# TOP.net
KiCad netlist of a schematic drawn in Altium Designer
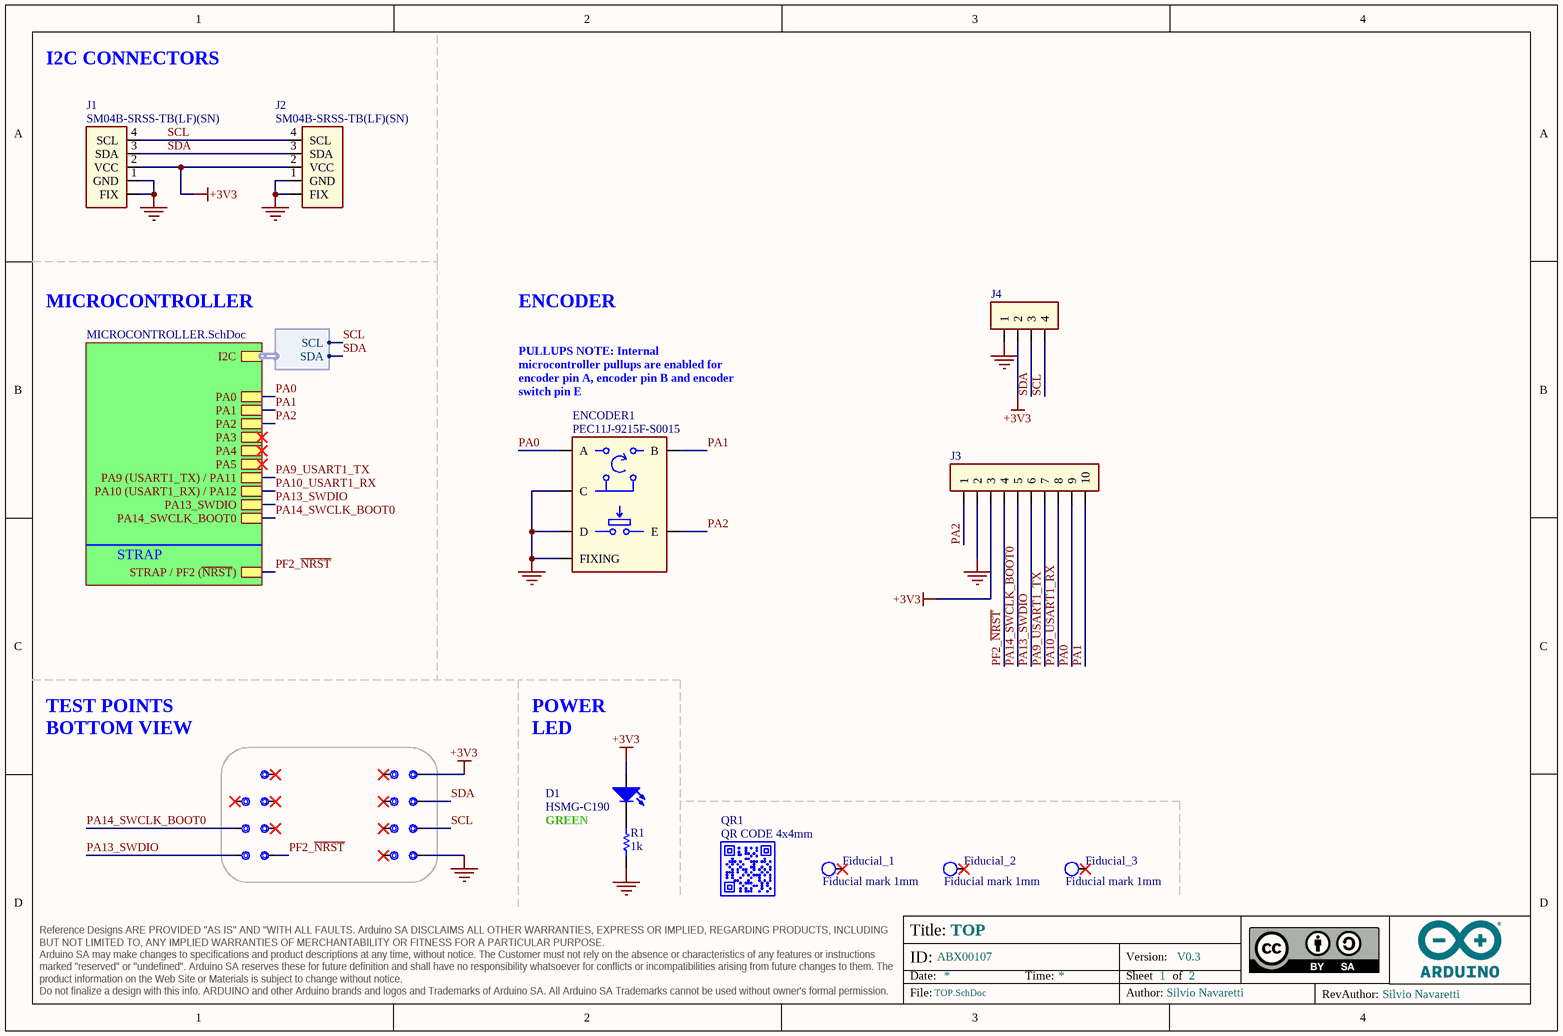
[diagram p0: TOP.SchDoc]

(export (version "E")
  (design (tool "Eeschema 10.0.6"))
  (components
    (comp (ref "3V3")
      (value "Test point 1.00mm")
      (footprint "TP-1.00MM")
      (fields (field (name "MANUFACTURER") "This is not a component"))
      (libsource (lib "Clean") (part "TESTPOINT"))
    )
    (comp (ref "D1")
      (value "HSMG-C190")
      (footprint "LEDC1608X80N-AK")
      (description "LED SMD 0603 GREEN/568 15mcd 120^")
      (fields (field (name "MANUFACTURER") "Broadcom"))
      (libsource (lib "Clean") (part "LED"))
    )
    (comp (ref "ENCODER1")
      (value "PEC11J-9215F-S0015")
      (footprint "PEC11J-9215F-S0015")
      (description "ENCODER 2b quadrature, 15PPR, 30 detents, shaft 15mm D-Cut, switch 350+-100gf, SMD 15x18x20mm")
      (fields (field (name "MANUFACTURER") "Bourns"))
      (libsource (lib "Clean") (part "PEC11J-9215F-S0015"))
    )
    (comp (ref "Fiducial_1")
      (value "Fiducial mark 1mm")
      (footprint "Fiducial mark 1mm-Footprint-1")
      (description "Fiducial mark 1mm clearance 2mm")
      (libsource (lib "Clean") (part "Fiducial mark 1mm"))
    )
    (comp (ref "Fiducial_2")
      (value "Fiducial mark 1mm")
      (footprint "Fiducial mark 1mm-Footprint-1")
      (description "Fiducial mark 1mm clearance 2mm")
      (libsource (lib "Clean") (part "Fiducial mark 1mm"))
    )
    (comp (ref "Fiducial_3")
      (value "Fiducial mark 1mm")
      (footprint "Fiducial mark 1mm-Footprint-1")
      (description "Fiducial mark 1mm clearance 2mm")
      (libsource (lib "Clean") (part "Fiducial mark 1mm"))
    )
    (comp (ref "GND")
      (value "Test point 1.00mm")
      (footprint "TP-1.00MM")
      (fields (field (name "MANUFACTURER") "This is not a component"))
      (libsource (lib "Clean") (part "TESTPOINT"))
    )
    (comp (ref "J1")
      (value "SM04B-SRSS-TB(LF)(SN)")
      (footprint "SM04B-SRSS-TB(LF)(SN)-Footprint-1")
      (description "CONN JST 4POS SIDE 1MM TIN QWIIC")
      (fields (field (name "MANUFACTURER") "JST"))
      (libsource (lib "") (part "SM04B-SRSS-TB(LF)(SN)_1"))
    )
    (comp (ref "J2")
      (value "SM04B-SRSS-TB(LF)(SN)")
      (footprint "SM04B-SRSS-TB(LF)(SN)-Footprint-1")
      (description "CONN JST 4POS SIDE 1MM TIN QWIIC")
      (fields (field (name "MANUFACTURER") "JST"))
      (libsource (lib "Clean") (part "SM04B-SRSS-TB(LF)(SN)"))
    )
    (comp (ref "J3")
      (value "HEADER TH 2.54mm VERT. 1x010POS")
      (footprint "PIN HEADER 2.54mm VERT. 1x10POS")
      (libsource (lib "Clean") (part "PIN HEADER 2.54mm VERT. 1x10POS"))
    )
    (comp (ref "J4")
      (value "HEADER TH 2.54mm VERT. 1x004POS")
      (footprint "PIN HEADER 2.54mm VERT. 1x4POS-Footprint-1")
      (libsource (lib "Clean") (part "PIN HEADER 2.54mm VERT. 1x4POS"))
    )
    (comp (ref "NRST")
      (value "Test point 1.00mm")
      (footprint "TP-1.00MM")
      (fields (field (name "MANUFACTURER") "This is not a component"))
      (libsource (lib "Clean") (part "TESTPOINT"))
    )
    (comp (ref "PA6")
      (value "Test point 1.00mm")
      (footprint "TP-1.00MM")
      (fields (field (name "MANUFACTURER") "This is not a component"))
      (libsource (lib "Clean") (part "TESTPOINT"))
    )
    (comp (ref "PA7")
      (value "Test point 1.00mm")
      (footprint "TP-1.00MM")
      (fields (field (name "MANUFACTURER") "This is not a component"))
      (libsource (lib "Clean") (part "TESTPOINT"))
    )
    (comp (ref "PC14")
      (value "Test point 1.00mm")
      (footprint "TP-1.00MM")
      (fields (field (name "MANUFACTURER") "This is not a component"))
      (libsource (lib "Clean") (part "TESTPOINT"))
    )
    (comp (ref "PC15")
      (value "Test point 1.00mm")
      (footprint "TP-1.00MM")
      (fields (field (name "MANUFACTURER") "This is not a component"))
      (libsource (lib "Clean") (part "TESTPOINT"))
    )
    (comp (ref "QR1")
      (value "QR CODE 4x4mm")
      (footprint "QR CODE 4x4mm")
      (description "QR CODE 4x4mm on layer 34 (This is not a component)")
      (fields (field (name "PART NUMBER") "This is not a component"))
      (libsource (lib "Clean") (part "QR CODE 4x4mm"))
    )
    (comp (ref "R1")
      (value "1k")
      (footprint "RES-0402")
      (description "RES CHIP 0402 1k 1% 1/16W")
      (fields (field (name "PART NUMBER") "CRCW04021K00FKEDC") (field (name "TOLERANCE") "1%"))
      (libsource (lib "Clean") (part "RES"))
    )
    (comp (ref "SCL")
      (value "Test point 1.00mm")
      (footprint "TP-1.00MM")
      (fields (field (name "MANUFACTURER") "This is not a component"))
      (libsource (lib "Clean") (part "TESTPOINT"))
    )
    (comp (ref "SDA")
      (value "Test point 1.00mm")
      (footprint "TP-1.00MM")
      (fields (field (name "MANUFACTURER") "This is not a component"))
      (libsource (lib "Clean") (part "TESTPOINT"))
    )
    (comp (ref "SWCLK")
      (value "Test point 1.00mm")
      (footprint "TP-1.00MM")
      (fields (field (name "MANUFACTURER") "This is not a component"))
      (libsource (lib "Clean") (part "TESTPOINT"))
    )
    (comp (ref "SWDIO")
      (value "Test point 1.00mm")
      (footprint "TP-1.00MM")
      (fields (field (name "MANUFACTURER") "This is not a component"))
      (libsource (lib "Clean") (part "TESTPOINT"))
    )
    (comp (ref "TP9")
      (value "Test point 1.00mm")
      (footprint "TP-1.00MM")
      (fields (field (name "MANUFACTURER") "This is not a component"))
      (libsource (lib "Clean") (part "TESTPOINT"))
    )
    (comp (ref "TP10")
      (value "Test point 1.00mm")
      (footprint "TP-1.00MM")
      (fields (field (name "MANUFACTURER") "This is not a component"))
      (libsource (lib "Clean") (part "TESTPOINT"))
    )
    (comp (ref "TP11")
      (value "Test point 1.00mm")
      (footprint "TP-1.00MM")
      (fields (field (name "MANUFACTURER") "This is not a component"))
      (libsource (lib "Clean") (part "TESTPOINT"))
    )
    (comp (ref "TP12")
      (value "Test point 1.00mm")
      (footprint "TP-1.00MM")
      (fields (field (name "MANUFACTURER") "This is not a component"))
      (libsource (lib "Clean") (part "TESTPOINT"))
    )
  )
  (nets
    (net (code "2") (name "+3V3") (class "Default")
      (node (ref "3V3") (pin "X") (pinfunction "X_X") (pintype "passive"))
      (node (ref "D1") (pin "A") (pinfunction "A_A") (pintype "passive"))
      (node (ref "J1") (pin "2") (pinfunction "VCC_2") (pintype "passive"))
      (node (ref "J2") (pin "2") (pinfunction "VCC_2") (pintype "passive"))
      (node (ref "J3") (pin "3") (pinfunction "3_3") (pintype "passive"))
      (node (ref "J4") (pin "2") (pinfunction "2_2") (pintype "passive"))
    )
    (net (code "3") (name "/PA0") (class "Default")
      (node (ref "ENCODER1") (pin "A") (pinfunction "A_A") (pintype "passive"))
      (node (ref "J3") (pin "9") (pinfunction "9_9") (pintype "passive"))
    )
    (net (code "4") (name "/PA1") (class "Default")
      (node (ref "ENCODER1") (pin "B") (pinfunction "B_B") (pintype "passive"))
      (node (ref "J3") (pin "10") (pinfunction "10_10") (pintype "passive"))
    )
    (net (code "5") (name "/PA2") (class "Default")
      (node (ref "ENCODER1") (pin "E") (pinfunction "E_E") (pintype "passive"))
      (node (ref "J3") (pin "1") (pinfunction "1_1") (pintype "passive"))
    )
    (net (code "9") (name "/PA9_USART1_TX") (class "Default")
      (node (ref "J3") (pin "7") (pinfunction "7_7") (pintype "passive"))
    )
    (net (code "10") (name "/PA10_USART1_RX") (class "Default")
      (node (ref "J3") (pin "8") (pinfunction "8_8") (pintype "passive"))
    )
    (net (code "11") (name "/PA13_SWDIO") (class "Default")
      (node (ref "J3") (pin "6") (pinfunction "6_6") (pintype "passive"))
      (node (ref "SWCLK") (pin "X") (pinfunction "X_X") (pintype "passive"))
    )
    (net (code "12") (name "/PA14_SWCLK_BOOT0") (class "Default")
      (node (ref "J3") (pin "5") (pinfunction "5_5") (pintype "passive"))
      (node (ref "SWDIO") (pin "X") (pinfunction "X_X") (pintype "passive"))
    )
    (net (code "13") (name "/PF2_~{NRST}") (class "Default")
      (node (ref "J3") (pin "4") (pinfunction "4_4") (pintype "passive"))
      (node (ref "NRST") (pin "X") (pinfunction "X_X") (pintype "passive"))
    )
    (net (code "14") (name "/SCL") (class "Default")
      (node (ref "J1") (pin "4") (pinfunction "SCL_4") (pintype "passive"))
      (node (ref "J2") (pin "4") (pinfunction "SCL_4") (pintype "passive"))
      (node (ref "J4") (pin "4") (pinfunction "4_4") (pintype "passive"))
      (node (ref "SCL") (pin "X") (pinfunction "X_X") (pintype "passive"))
    )
    (net (code "15") (name "/SDA") (class "Default")
      (node (ref "J1") (pin "3") (pinfunction "SDA_3") (pintype "passive"))
      (node (ref "J2") (pin "3") (pinfunction "SDA_3") (pintype "passive"))
      (node (ref "J4") (pin "3") (pinfunction "3_3") (pintype "passive"))
      (node (ref "SDA") (pin "X") (pinfunction "X_X") (pintype "passive"))
    )
    (net (code "17") (name "GND") (class "Default")
      (node (ref "ENCODER1") (pin "C") (pinfunction "C_C") (pintype "passive"))
      (node (ref "ENCODER1") (pin "D") (pinfunction "D_D") (pintype "passive"))
      (node (ref "ENCODER1") (pin "FIXING") (pinfunction "FIXING_FIXING") (pintype "passive"))
      (node (ref "GND") (pin "X") (pinfunction "X_X") (pintype "passive"))
      (node (ref "J1") (pin "1") (pinfunction "GND_1") (pintype "passive"))
      (node (ref "J1") (pin "FIX") (pinfunction "FIX_FIX") (pintype "passive"))
      (node (ref "J2") (pin "1") (pinfunction "GND_1") (pintype "passive"))
      (node (ref "J2") (pin "FIX") (pinfunction "FIX_FIX") (pintype "passive"))
      (node (ref "J3") (pin "2") (pinfunction "2_2") (pintype "passive"))
      (node (ref "J4") (pin "1") (pinfunction "1_1") (pintype "passive"))
      (node (ref "R1") (pin "1") (pinfunction "1_1") (pintype "passive"))
    )
    (net (code "18") (name "Net-(D1-PadC)") (class "Default")
      (node (ref "D1") (pin "C") (pinfunction "C_C") (pintype "passive"))
      (node (ref "R1") (pin "2") (pinfunction "2_2") (pintype "passive"))
    )
    (net (code "19") (name "unconnected-(Fiducial_1-Pad1)") (class "Default")
      (node (ref "Fiducial_1") (pin "1") (pinfunction "1_1") (pintype "passive+no_connect"))
    )
    (net (code "20") (name "unconnected-(Fiducial_2-Pad1)") (class "Default")
      (node (ref "Fiducial_2") (pin "1") (pinfunction "1_1") (pintype "passive+no_connect"))
    )
    (net (code "21") (name "unconnected-(Fiducial_3-Pad1)") (class "Default")
      (node (ref "Fiducial_3") (pin "1") (pinfunction "1_1") (pintype "passive+no_connect"))
    )
    (net (code "22") (name "unconnected-(PA6-PadX)") (class "Default")
      (node (ref "PA6") (pin "X") (pinfunction "X_X") (pintype "passive+no_connect"))
    )
    (net (code "23") (name "unconnected-(PA7-PadX)") (class "Default")
      (node (ref "PA7") (pin "X") (pinfunction "X_X") (pintype "passive+no_connect"))
    )
    (net (code "24") (name "unconnected-(PC14-PadX)") (class "Default")
      (node (ref "PC14") (pin "X") (pinfunction "X_X") (pintype "passive+no_connect"))
    )
    (net (code "25") (name "unconnected-(PC15-PadX)") (class "Default")
      (node (ref "PC15") (pin "X") (pinfunction "X_X") (pintype "passive+no_connect"))
    )
    (net (code "26") (name "unconnected-(TP9-PadX)") (class "Default")
      (node (ref "TP9") (pin "X") (pinfunction "X_X") (pintype "passive+no_connect"))
    )
    (net (code "27") (name "unconnected-(TP10-PadX)") (class "Default")
      (node (ref "TP10") (pin "X") (pinfunction "X_X") (pintype "passive+no_connect"))
    )
    (net (code "28") (name "unconnected-(TP11-PadX)") (class "Default")
      (node (ref "TP11") (pin "X") (pinfunction "X_X") (pintype "passive+no_connect"))
    )
    (net (code "29") (name "unconnected-(TP12-PadX)") (class "Default")
      (node (ref "TP12") (pin "X") (pinfunction "X_X") (pintype "passive+no_connect"))
    )
  )
)
